# OpAmpSCH.net
KiCad netlist of a schematic drawn in Altium Designer
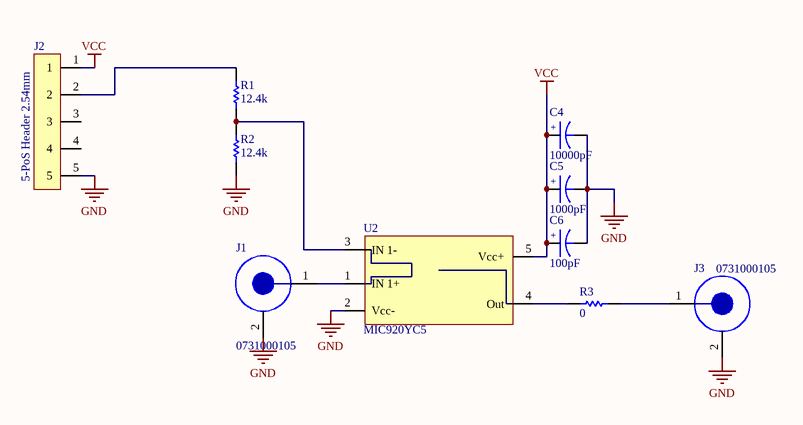
[diagram p0: OpAmpSCH.SchDoc]

(export (version "E")
  (design (tool "Eeschema 10.0.6"))
  (components
    (comp (ref "C4")
      (value "10000pF")
      (footprint "0603C")
      (description "Cap Poly")
      (libsource (lib "GENERIC_LIB") (part "CPoly"))
    )
    (comp (ref "C5")
      (value "1000pF")
      (footprint "0603C")
      (description "Cap Poly")
      (libsource (lib "GENERIC_LIB") (part "CPoly"))
    )
    (comp (ref "C6")
      (value "100pF")
      (footprint "0603C")
      (description "Cap Poly")
      (libsource (lib "GENERIC_LIB") (part "CPoly"))
    )
    (comp (ref "J1")
      (value "0731000105")
      (footprint "0731000105")
      (description "BNC Connector Jack, Female Socket 50Ohm Through Hole, Right Angle Solder")
      (libsource (lib "CON_LIB") (part "0731000105"))
    )
    (comp (ref "J2")
      (value "5-PoS Header 2.54mm")
      (footprint "2.54mm Pitch Header")
      (libsource (lib "CON_LIB") (part "5-PoS Header 2.54mm"))
    )
    (comp (ref "J3")
      (value "0731000105")
      (footprint "0731000105")
      (description "BNC Connector Jack, Female Socket 50Ohm Through Hole, Right Angle Solder")
      (libsource (lib "CON_LIB") (part "0731000105"))
    )
    (comp (ref "R1")
      (value "12.4k")
      (footprint "0603C")
      (description "Resistor")
      (fields (field (name "TOLERANCE") "5%"))
      (libsource (lib "GENERIC_LIB") (part "R"))
    )
    (comp (ref "R2")
      (value "12.4k")
      (footprint "0603C")
      (description "Resistor")
      (fields (field (name "TOLERANCE") "5%"))
      (libsource (lib "GENERIC_LIB") (part "R"))
    )
    (comp (ref "R3")
      (value "0")
      (footprint "1206C")
      (description "Resistor")
      (fields (field (name "TOLERANCE") "5%"))
      (libsource (lib "GENERIC_LIB") (part "R"))
    )
    (comp (ref "U2")
      (value "MIC920YC5")
      (footprint "MIC920")
      (description "General Purpose Amplifier 1 Circuit SC-70-5")
      (libsource (lib "ANALOG_LIB") (part "MIC920YC5-TR"))
    )
  )
  (nets
    (net (code "1") (name "GND") (class "Default")
      (node (ref "C4") (pin "2") (pinfunction "2_2") (pintype "passive"))
      (node (ref "C5") (pin "2") (pinfunction "2_2") (pintype "passive"))
      (node (ref "C6") (pin "2") (pinfunction "2_2") (pintype "passive"))
      (node (ref "J1") (pin "2") (pinfunction "2_2") (pintype "passive"))
      (node (ref "J2") (pin "5") (pinfunction "5_5") (pintype "passive"))
      (node (ref "J3") (pin "2") (pinfunction "2_2") (pintype "passive"))
      (node (ref "R2") (pin "1") (pinfunction "1_1") (pintype "passive"))
      (node (ref "U2") (pin "2") (pinfunction "Vcc-_2") (pintype "passive"))
    )
    (net (code "2") (name "Net-(J2-Pad2)") (class "Default")
      (node (ref "J2") (pin "2") (pinfunction "2_2") (pintype "passive"))
      (node (ref "R1") (pin "2") (pinfunction "2_2") (pintype "passive"))
    )
    (net (code "3") (name "Net-(J3-Pad1)") (class "Default")
      (node (ref "J3") (pin "1") (pinfunction "1_1") (pintype "passive"))
      (node (ref "R3") (pin "2") (pinfunction "2_2") (pintype "passive"))
    )
    (net (code "4") (name "Net-(U2-IN_1+)") (class "Default")
      (node (ref "J1") (pin "1") (pinfunction "1_1") (pintype "passive"))
      (node (ref "U2") (pin "1") (pinfunction "IN_1+_1") (pintype "passive"))
    )
    (net (code "5") (name "Net-(U2-IN_1-)") (class "Default")
      (node (ref "R1") (pin "1") (pinfunction "1_1") (pintype "passive"))
      (node (ref "R2") (pin "2") (pinfunction "2_2") (pintype "passive"))
      (node (ref "U2") (pin "3") (pinfunction "IN_1-_3") (pintype "passive"))
    )
    (net (code "6") (name "Net-(U2-Out)") (class "Default")
      (node (ref "R3") (pin "1") (pinfunction "1_1") (pintype "passive"))
      (node (ref "U2") (pin "4") (pinfunction "Out_4") (pintype "passive"))
    )
    (net (code "7") (name "VCC") (class "Default")
      (node (ref "C4") (pin "1") (pinfunction "1_1") (pintype "passive"))
      (node (ref "C5") (pin "1") (pinfunction "1_1") (pintype "passive"))
      (node (ref "C6") (pin "1") (pinfunction "1_1") (pintype "passive"))
      (node (ref "J2") (pin "1") (pinfunction "1_1") (pintype "passive"))
      (node (ref "U2") (pin "5") (pinfunction "Vcc+_5") (pintype "passive"))
    )
    (net (code "8") (name "unconnected-(J2-Pad3)") (class "Default")
      (node (ref "J2") (pin "3") (pinfunction "3_3") (pintype "passive"))
    )
    (net (code "9") (name "unconnected-(J2-Pad4)") (class "Default")
      (node (ref "J2") (pin "4") (pinfunction "4_4") (pintype "passive"))
    )
  )
)
